# VanoDolbano.net
KiCad netlist of a schematic drawn in Altium Designer
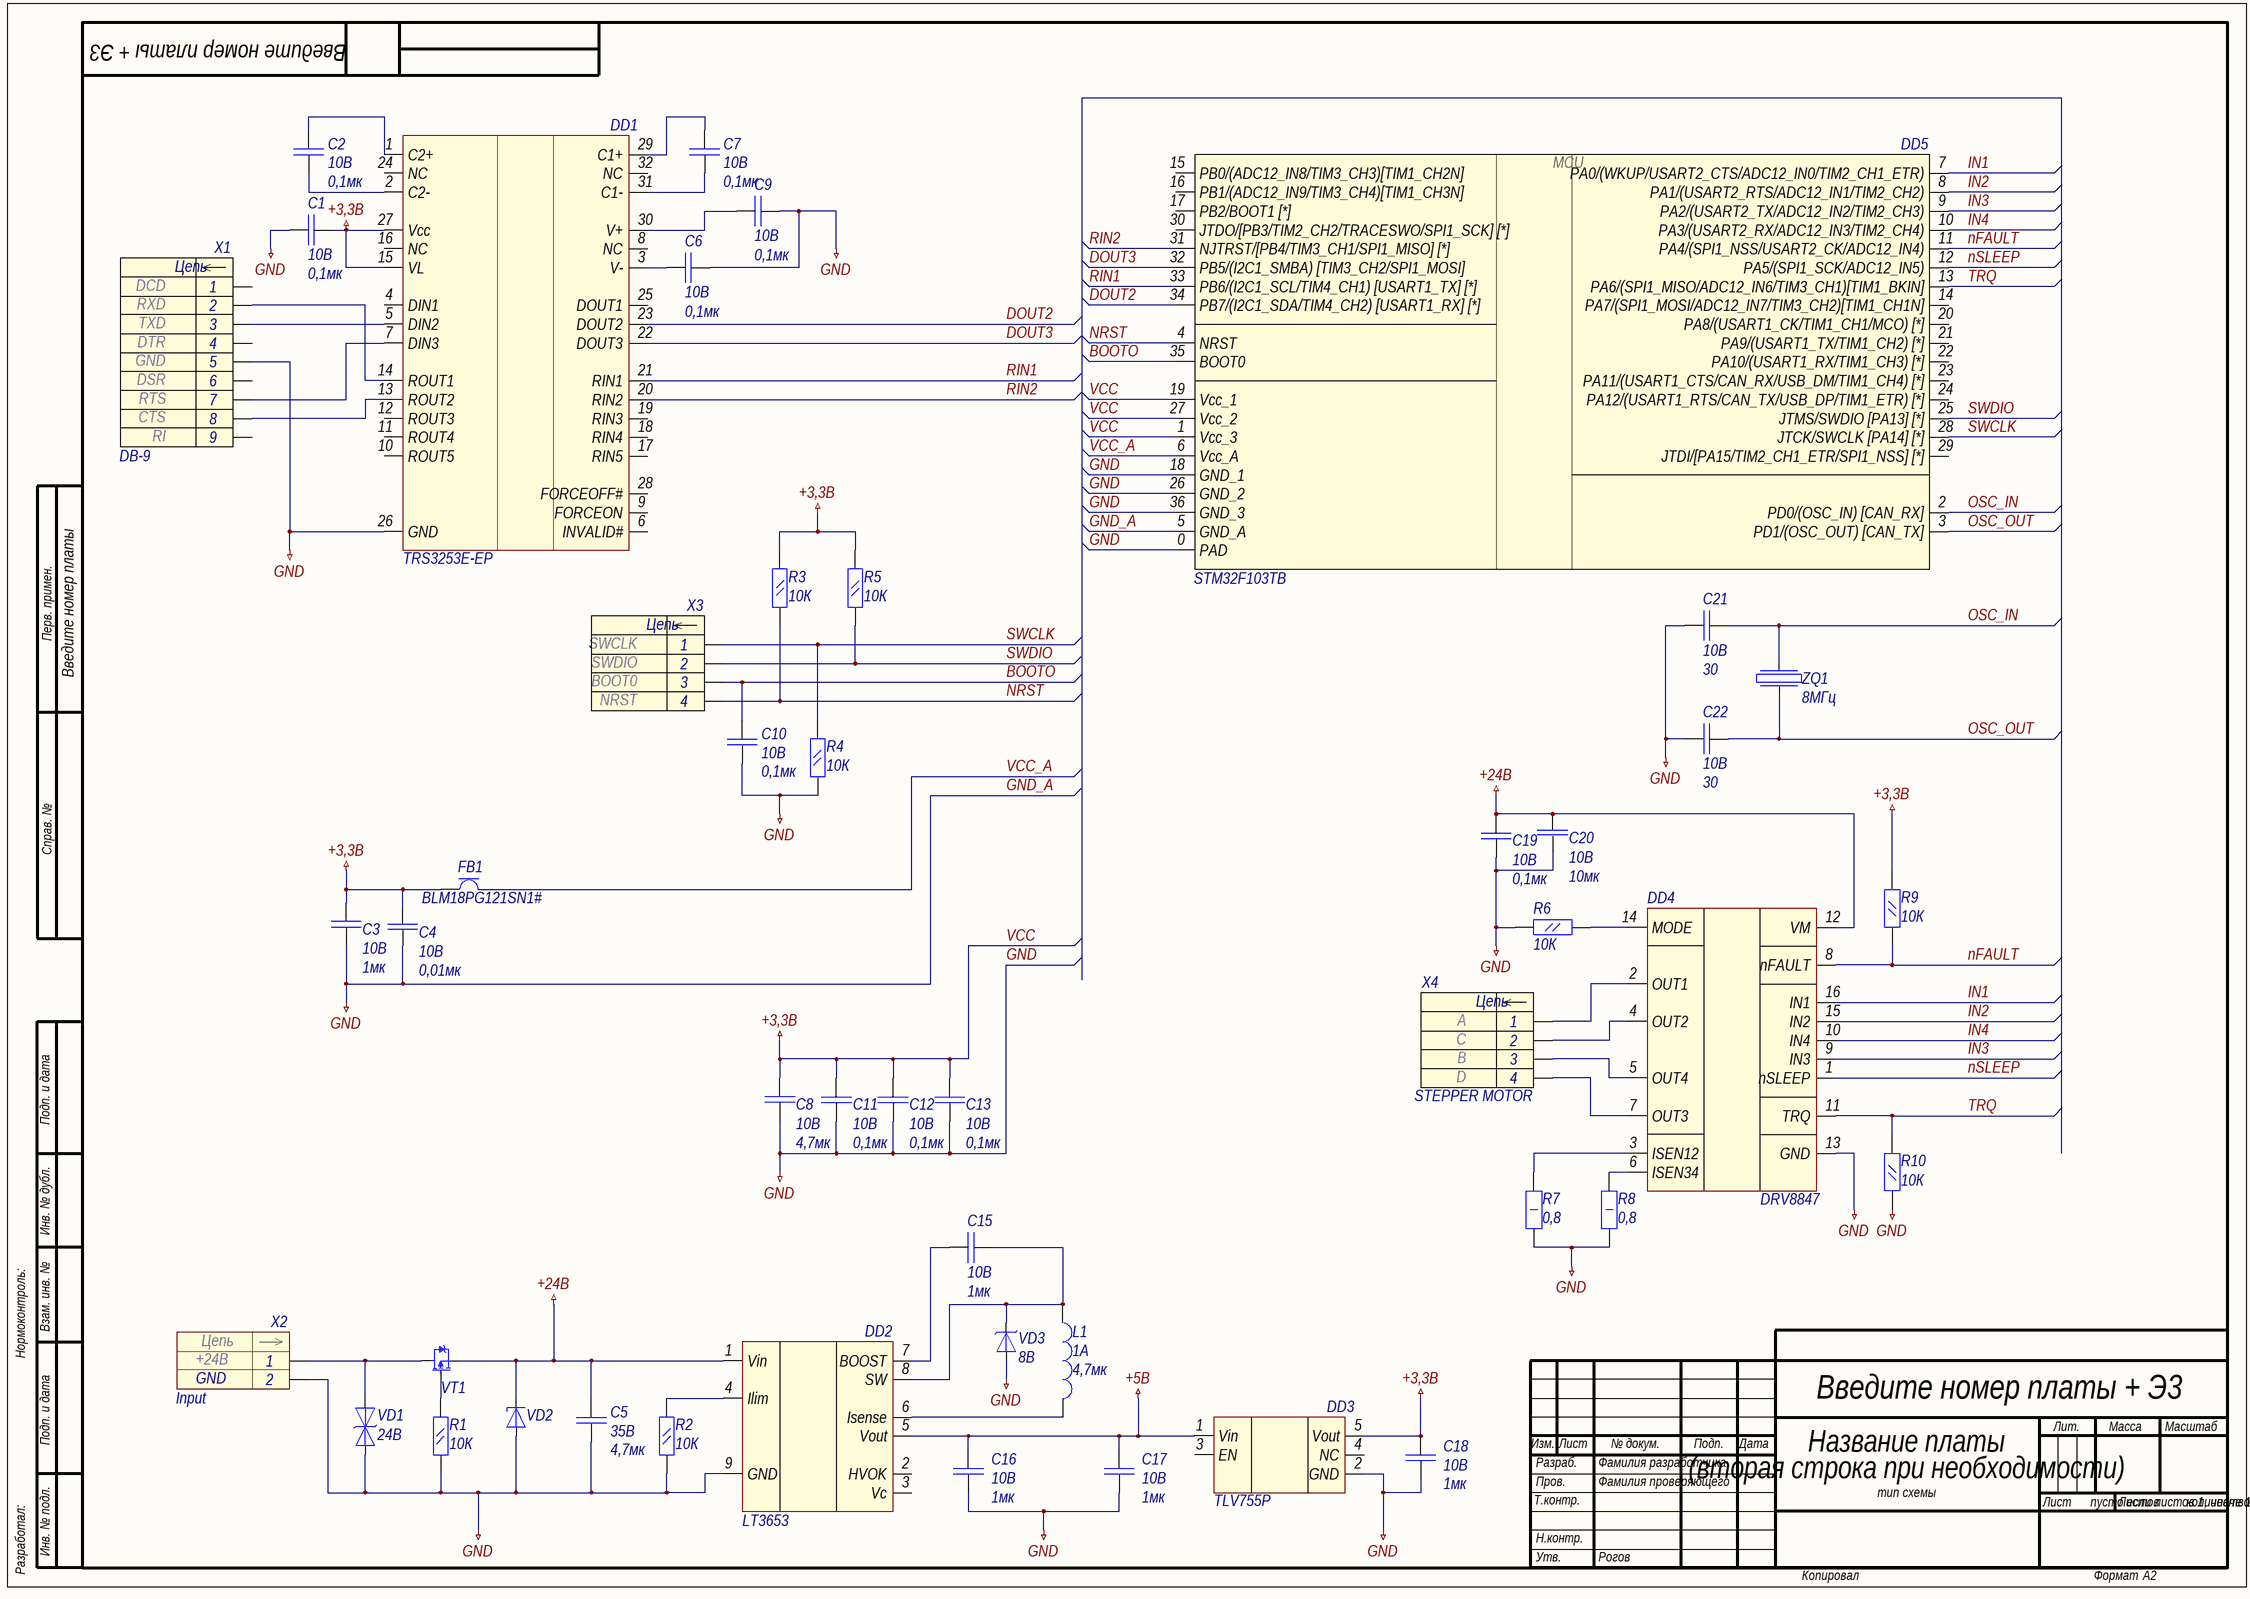
[diagram p0: VanoDolbano.schdoc]

(export (version "E")
  (design (tool "Eeschema 10.0.6"))
  (components
    (comp (ref "C1")
      (value "Capacitor")
      (footprint "CH0402C")
      (fields (field (name "VOLTAGE") "10В") (field (name "CAPACITANCE") "0,1мк"))
      (libsource (lib "GOST_Capacitors") (part "Capacitor"))
    )
    (comp (ref "C2")
      (value "Capacitor")
      (footprint "CH0402C")
      (fields (field (name "VOLTAGE") "10В") (field (name "CAPACITANCE") "0,1мк"))
      (libsource (lib "GOST_Capacitors") (part "Capacitor"))
    )
    (comp (ref "C3")
      (value "Capacitor")
      (footprint "CH0201C")
      (fields (field (name "VOLTAGE") "10В") (field (name "CAPACITANCE") "1мк"))
      (libsource (lib "GOST_Capacitors") (part "Capacitor"))
    )
    (comp (ref "C4")
      (value "Capacitor")
      (footprint "CH0402C")
      (fields (field (name "VOLTAGE") "10В") (field (name "CAPACITANCE") "0,01мк"))
      (libsource (lib "") (part "Capacitor_1"))
    )
    (comp (ref "C5")
      (value "Capacitor")
      (footprint "CH0603C")
      (fields (field (name "VOLTAGE") "35В") (field (name "CAPACITANCE") "4,7мк"))
      (libsource (lib "GOST_Capacitors") (part "Capacitor"))
    )
    (comp (ref "C6")
      (value "Capacitor")
      (footprint "CH0402C")
      (fields (field (name "VOLTAGE") "10В") (field (name "CAPACITANCE") "0,1мк"))
      (libsource (lib "GOST_Capacitors") (part "Capacitor"))
    )
    (comp (ref "C7")
      (value "Capacitor")
      (footprint "CH0402C")
      (fields (field (name "VOLTAGE") "10В") (field (name "CAPACITANCE") "0,1мк"))
      (libsource (lib "GOST_Capacitors") (part "Capacitor"))
    )
    (comp (ref "C8")
      (value "Capacitor")
      (footprint "CH0402C")
      (fields (field (name "VOLTAGE") "10В") (field (name "CAPACITANCE") "4,7мк"))
      (libsource (lib "GOST_Capacitors") (part "Capacitor"))
    )
    (comp (ref "C9")
      (value "Capacitor")
      (footprint "CH0402C")
      (fields (field (name "VOLTAGE") "10В") (field (name "CAPACITANCE") "0,1мк"))
      (libsource (lib "GOST_Capacitors") (part "Capacitor"))
    )
    (comp (ref "C10")
      (value "Capacitor")
      (footprint "CH0402C")
      (fields (field (name "VOLTAGE") "10В") (field (name "CAPACITANCE") "0,1мк"))
      (libsource (lib "GOST_Capacitors") (part "Capacitor"))
    )
    (comp (ref "C11")
      (value "Capacitor")
      (footprint "CH0402C")
      (fields (field (name "VOLTAGE") "10В") (field (name "CAPACITANCE") "0,1мк"))
      (libsource (lib "GOST_Capacitors") (part "Capacitor"))
    )
    (comp (ref "C12")
      (value "Capacitor")
      (footprint "CH0402C")
      (fields (field (name "VOLTAGE") "10В") (field (name "CAPACITANCE") "0,1мк"))
      (libsource (lib "GOST_Capacitors") (part "Capacitor"))
    )
    (comp (ref "C13")
      (value "Capacitor")
      (footprint "CH0402C")
      (fields (field (name "VOLTAGE") "10В") (field (name "CAPACITANCE") "0,1мк"))
      (libsource (lib "GOST_Capacitors") (part "Capacitor"))
    )
    (comp (ref "C15")
      (value "Capacitor")
      (footprint "CH0201C")
      (fields (field (name "VOLTAGE") "10В") (field (name "CAPACITANCE") "1мк"))
      (libsource (lib "GOST_Capacitors") (part "Capacitor"))
    )
    (comp (ref "C16")
      (value "Capacitor")
      (footprint "CH0201C")
      (fields (field (name "VOLTAGE") "10В") (field (name "CAPACITANCE") "1мк"))
      (libsource (lib "GOST_Capacitors") (part "Capacitor"))
    )
    (comp (ref "C17")
      (value "Capacitor")
      (footprint "CH0201C")
      (fields (field (name "VOLTAGE") "10В") (field (name "CAPACITANCE") "1мк"))
      (libsource (lib "GOST_Capacitors") (part "Capacitor"))
    )
    (comp (ref "C18")
      (value "Capacitor")
      (footprint "CH0201C")
      (fields (field (name "VOLTAGE") "10В") (field (name "CAPACITANCE") "1мк"))
      (libsource (lib "GOST_Capacitors") (part "Capacitor"))
    )
    (comp (ref "C19")
      (value "Capacitor")
      (footprint "CH0402C")
      (fields (field (name "VOLTAGE") "10В") (field (name "CAPACITANCE") "0,1мк"))
      (libsource (lib "GOST_Capacitors") (part "Capacitor"))
    )
    (comp (ref "C20")
      (value "Capacitor")
      (footprint "CH0402C")
      (fields (field (name "VOLTAGE") "10В") (field (name "CAPACITANCE") "10мк"))
      (libsource (lib "") (part "Capacitor_1"))
    )
    (comp (ref "C21")
      (value "Capacitor")
      (footprint "CH0201C")
      (fields (field (name "VOLTAGE") "10В") (field (name "CAPACITANCE") "30"))
      (libsource (lib "GOST_Capacitors") (part "Capacitor"))
    )
    (comp (ref "C22")
      (value "Capacitor")
      (footprint "CH0201C")
      (fields (field (name "VOLTAGE") "10В") (field (name "CAPACITANCE") "30"))
      (libsource (lib "GOST_Capacitors") (part "Capacitor"))
    )
    (comp (ref "DD1")
      (value "TRS3253E-EP")
      (footprint "TRS3253E-EP")
      (description "UART - RS232")
      (libsource (lib "GOST_lib_devices") (part "TRS3253E-EP"))
    )
    (comp (ref "DD2")
      (value "LT3653")
      (footprint "LT3653")
      (description "7.5~30 to 5")
      (libsource (lib "GOST_lib_devices") (part "LT3653"))
    )
    (comp (ref "DD3")
      (value "TLV755P")
      (footprint "SOT23-5")
      (libsource (lib "GOST_lib_devices") (part "LDO +3.3V"))
    )
    (comp (ref "DD4")
      (value "DRV8847")
      (footprint "DRV8847")
      (libsource (lib "GOST_lib_devices") (part "DRV8847"))
    )
    (comp (ref "DD5")
      (value "STM32F103TB")
      (footprint "PcbLib1:STM32_f103_36Pins")
      (description "Микроконтроллер")
      (libsource (lib "uMC") (part "STM32F103TB"))
    )
    (comp (ref "FB1")
      (value "Ferrite bead")
      (footprint "CH0603L")
      (fields (field (name "MODEL") "BLM18PG121SN1#"))
      (libsource (lib "GOST_Inductors") (part "Ferrite bead"))
    )
    (comp (ref "L1")
      (value "Inductor")
      (footprint "CH0805L")
      (fields (field (name "MAX CURRENT") "1А") (field (name "INDUCTANCE") "4,7мк"))
      (libsource (lib "GOST_Inductors") (part "Inductor"))
    )
    (comp (ref "R1")
      (value "Res_0.125")
      (footprint "CH0402R")
      (fields (field (name "IMPEDANCE") "10К"))
      (libsource (lib "GOST_Resistors") (part "Res_0.125"))
    )
    (comp (ref "R2")
      (value "Res_0.125")
      (footprint "CH0402R")
      (fields (field (name "IMPEDANCE") "10К"))
      (libsource (lib "GOST_Resistors") (part "Res_0.125"))
    )
    (comp (ref "R3")
      (value "Res_0.125")
      (footprint "CH0805R")
      (fields (field (name "IMPEDANCE") "10К"))
      (libsource (lib "") (part "Res_0.125_1"))
    )
    (comp (ref "R4")
      (value "Res_0.125")
      (footprint "CH0805R")
      (fields (field (name "IMPEDANCE") "10К"))
      (libsource (lib "") (part "Res_0.125_1"))
    )
    (comp (ref "R5")
      (value "Res_0.125")
      (footprint "CH0805R")
      (fields (field (name "IMPEDANCE") "10К"))
      (libsource (lib "") (part "Res_0.125_1"))
    )
    (comp (ref "R6")
      (value "Res_0.125")
      (footprint "CH0402R")
      (fields (field (name "IMPEDANCE") "10К"))
      (libsource (lib "GOST_Resistors") (part "Res_0.125"))
    )
    (comp (ref "R7")
      (value "Res_1")
      (footprint "CH2010R")
      (fields (field (name "POWER") "1Вт") (field (name "IMPEDANCE") "0,8"))
      (libsource (lib "GOST_Resistors") (part "Res_1"))
    )
    (comp (ref "R8")
      (value "Res_1")
      (footprint "CH2010R")
      (fields (field (name "POWER") "1Вт") (field (name "IMPEDANCE") "0,8"))
      (libsource (lib "GOST_Resistors") (part "Res_1"))
    )
    (comp (ref "R9")
      (value "Res_0.125")
      (footprint "CH0402R")
      (fields (field (name "IMPEDANCE") "10К"))
      (libsource (lib "GOST_Resistors") (part "Res_0.125"))
    )
    (comp (ref "R10")
      (value "Res_0.125")
      (footprint "CH0402R")
      (fields (field (name "IMPEDANCE") "10К"))
      (libsource (lib "GOST_Resistors") (part "Res_0.125"))
    )
    (comp (ref "VD1")
      (value "TVS-diod_simmetrical")
      (footprint "standard:SOD323")
      (fields (field (name "MANUFACTURER") "Torex Semiconductor") (field (name "THRESH_VOLTAGE") "24В"))
      (libsource (lib "GOST_Diodes") (part "TVS-diod_simmetrical"))
    )
    (comp (ref "VD2")
      (value "Diod Zener")
      (footprint "standard:SOD123")
      (libsource (lib "GOST_Diodes") (part "Diod Zener"))
    )
    (comp (ref "VD3")
      (value "TVS-diod_directed")
      (footprint "SOD123W")
      (fields (field (name "MANUFACTURER") "Nexperia") (field (name "CLAMPING_VOLTAGE") "8В"))
      (libsource (lib "GOST_Diodes") (part "TVS-diod_directed"))
    )
    (comp (ref "VT1")
      (value "P-Channel")
      (footprint "SOT23_132")
      (libsource (lib "GOST_Transistors") (part "P-Channel"))
    )
    (comp (ref "X1")
      (value "DB-9")
      (footprint "CON: DB-9F")
      (fields
        (field (name "1") "DCD")
        (field (name "2") "RXD")
        (field (name "3") "TXD")
        (field (name "4") "DTR")
        (field (name "5") "GND")
        (field (name "6") "DSR")
        (field (name "7") "RTS")
        (field (name "8") "CTS")
        (field (name "9") "RI")
      )
      (libsource (lib "GOST_lib_connectors") (part "9_pins"))
    )
    (comp (ref "X2")
      (value "Input")
      (footprint "CON: 163-179PH-EX")
      (fields (field (name "VCC") "+24В"))
      (libsource (lib "GOST_lib_connectors") (part "2_pins"))
    )
    (comp (ref "X3")
      (value "4_pins")
      (footprint "CON: CWF-4R")
      (fields
        (field (name "2") "SWDIO")
        (field (name "3") "BOOT0")
        (field (name "1") "SWCLK")
        (field (name "4") "NRST")
      )
      (libsource (lib "GOST_lib_connectors") (part "4_pins"))
    )
    (comp (ref "X4")
      (value "STEPPER MOTOR")
      (footprint "CON: CWF-4R")
      (description "Bipolar Stepper Motor 200 Step 0.35A 12VDC")
      (fields (field (name "2") "C") (field (name "3") "B") (field (name "1") "A") (field (name "4") "D"))
      (libsource (lib "GOST_lib_connectors") (part "4_pins"))
    )
    (comp (ref "ZQ1")
      (value "Oscillator")
      (footprint "OSC: 5032")
      (fields (field (name "FREQ") "8МГц"))
      (libsource (lib "GOST_Miscelanuious") (part "Oscillator"))
    )
  )
  (nets
    (net (code "1") (name "+3,3В") (class "Default")
      (node (ref "C1") (pin "2") (pinfunction "C1-_2") (pintype "power_in"))
      (node (ref "C11") (pin "1") (pinfunction "C1+_1") (pintype "power_in"))
      (node (ref "C12") (pin "1") (pinfunction "C1+_1") (pintype "power_in"))
      (node (ref "C13") (pin "1") (pinfunction "C1+_1") (pintype "power_in"))
      (node (ref "C18") (pin "1") (pinfunction "C1+_1") (pintype "power_in"))
      (node (ref "C3") (pin "2") (pinfunction "C1-_2") (pintype "power_in"))
      (node (ref "C4") (pin "1") (pinfunction "С+_1") (pintype "power_in"))
      (node (ref "C8") (pin "2") (pinfunction "C1-_2") (pintype "power_in"))
      (node (ref "DD1") (pin "15") (pinfunction "VL_15") (pintype "power_in"))
      (node (ref "DD1") (pin "27") (pinfunction "Vcc_27") (pintype "power_in"))
      (node (ref "DD3") (pin "5") (pinfunction "Vout_5") (pintype "power_in"))
      (node (ref "DD5") (pin "1") (pinfunction "Vcc_3_1") (pintype "passive"))
      (node (ref "DD5") (pin "19") (pinfunction "Vcc_1_19") (pintype "passive"))
      (node (ref "DD5") (pin "27") (pinfunction "Vcc_2_27") (pintype "passive"))
      (node (ref "FB1") (pin "1") (pintype "power_in"))
      (node (ref "R3") (pin "1") (pinfunction "C1-_1") (pintype "power_in"))
      (node (ref "R5") (pin "2") (pinfunction "C1-_2") (pintype "power_in"))
      (node (ref "R9") (pin "1") (pinfunction "1_1") (pintype "power_in"))
    )
    (net (code "2") (name "+5В") (class "Default")
      (node (ref "C16") (pin "1") (pinfunction "C1+_1") (pintype "power_in"))
      (node (ref "C17") (pin "1") (pinfunction "C1+_1") (pintype "power_in"))
      (node (ref "DD2") (pin "5") (pinfunction "Vout_5") (pintype "power_in"))
      (node (ref "DD3") (pin "1") (pinfunction "Vin_1") (pintype "power_in"))
    )
    (net (code "3") (name "+24В") (class "Default")
      (node (ref "C19") (pin "1") (pinfunction "C1+_1") (pintype "power_in"))
      (node (ref "C20") (pin "1") (pinfunction "С+_1") (pintype "power_in"))
      (node (ref "C5") (pin "1") (pinfunction "C1+_1") (pintype "power_in"))
      (node (ref "DD2") (pin "1") (pinfunction "Vin_1") (pintype "power_in"))
      (node (ref "DD4") (pin "12") (pinfunction "VM_12") (pintype "power_in"))
      (node (ref "VD2") (pin "2") (pinfunction "C_2") (pintype "passive"))
      (node (ref "VT1") (pin "3") (pinfunction "S_3") (pintype "passive"))
    )
    (net (code "4") (name "/BOOTO") (class "Default")
      (node (ref "C10") (pin "1") (pinfunction "C1+_1") (pintype "power_in"))
      (node (ref "DD5") (pin "35") (pinfunction "BOOT0_35") (pintype "passive"))
      (node (ref "X3") (pin "3") (pinfunction "3_3") (pintype "passive"))
    )
    (net (code "5") (name "/DOUT2") (class "Default")
      (node (ref "DD1") (pin "23") (pinfunction "DOUT2_23") (pintype "power_in"))
      (node (ref "DD5") (pin "34") (pinfunction "PB7/(I2C1_SDA/TIM4_CH2)_[USART1_RX]_[*]_34") (pintype "passive"))
    )
    (net (code "6") (name "/DOUT3") (class "Default")
      (node (ref "DD1") (pin "22") (pinfunction "DOUT3_22") (pintype "power_in"))
      (node (ref "DD5") (pin "32") (pinfunction "PB5/(I2C1_SMBA)_[TIM3_CH2/SPI1_MOSI]_32") (pintype "passive"))
    )
    (net (code "7") (name "/IN1") (class "Default")
      (node (ref "DD4") (pin "16") (pinfunction "IN1_16") (pintype "power_in"))
      (node (ref "DD5") (pin "7") (pinfunction "PA0/(WKUP/USART2_CTS/ADC12_IN0/TIM2_CH1_ETR)_7") (pintype "passive"))
    )
    (net (code "8") (name "/IN2") (class "Default")
      (node (ref "DD4") (pin "15") (pinfunction "IN2_15") (pintype "power_in"))
      (node (ref "DD5") (pin "8") (pinfunction "PA1/(USART2_RTS/ADC12_IN1/TIM2_CH2)_8") (pintype "passive"))
    )
    (net (code "9") (name "/IN3") (class "Default")
      (node (ref "DD4") (pin "9") (pinfunction "IN3_9") (pintype "power_in"))
      (node (ref "DD5") (pin "9") (pinfunction "PA2/(USART2_TX/ADC12_IN2/TIM2_CH3)_9") (pintype "passive"))
    )
    (net (code "10") (name "/IN4") (class "Default")
      (node (ref "DD4") (pin "10") (pinfunction "IN4_10") (pintype "power_in"))
      (node (ref "DD5") (pin "10") (pinfunction "PA3/(USART2_RX/ADC12_IN3/TIM2_CH4)_10") (pintype "passive"))
    )
    (net (code "11") (name "/NRST") (class "Default")
      (node (ref "DD5") (pin "4") (pinfunction "NRST_4") (pintype "passive"))
      (node (ref "R3") (pin "2") (pinfunction "C1-_2") (pintype "power_in"))
      (node (ref "X3") (pin "4") (pinfunction "4_4") (pintype "passive"))
    )
    (net (code "12") (name "/OSC_IN") (class "Default")
      (node (ref "C21") (pin "1") (pinfunction "C1+_1") (pintype "power_in"))
      (node (ref "DD5") (pin "2") (pinfunction "PD0/(OSC_IN)_[CAN_RX]_2") (pintype "passive"))
      (node (ref "ZQ1") (pin "1") (pintype "passive"))
    )
    (net (code "13") (name "/OSC_OUT") (class "Default")
      (node (ref "C22") (pin "1") (pinfunction "C1+_1") (pintype "power_in"))
      (node (ref "DD5") (pin "3") (pinfunction "PD1/(OSC_OUT)_[CAN_TX]_3") (pintype "passive"))
      (node (ref "ZQ1") (pin "3") (pintype "passive"))
    )
    (net (code "14") (name "/RIN1") (class "Default")
      (node (ref "DD1") (pin "21") (pinfunction "RIN1_21") (pintype "power_in"))
      (node (ref "DD5") (pin "33") (pinfunction "PB6/(I2C1_SCL/TIM4_CH1)_[USART1_TX]_[*]_33") (pintype "passive"))
    )
    (net (code "15") (name "/RIN2") (class "Default")
      (node (ref "DD1") (pin "20") (pinfunction "RIN2_20") (pintype "power_in"))
      (node (ref "DD5") (pin "31") (pinfunction "NJTRST/[PB4/TIM3_CH1/SPI1_MISO]_[*]_31") (pintype "passive"))
    )
    (net (code "16") (name "/SWCLK") (class "Default")
      (node (ref "DD5") (pin "28") (pinfunction "JTCK/SWCLK_[PA14]_[*]_28") (pintype "passive"))
      (node (ref "R4") (pin "2") (pinfunction "C1-_2") (pintype "power_in"))
      (node (ref "X3") (pin "1") (pinfunction "1_1") (pintype "passive"))
    )
    (net (code "17") (name "/SWDIO") (class "Default")
      (node (ref "DD5") (pin "25") (pinfunction "JTMS/SWDIO_[PA13]_[*]_25") (pintype "passive"))
      (node (ref "R5") (pin "1") (pinfunction "C1-_1") (pintype "power_in"))
      (node (ref "X3") (pin "2") (pinfunction "2_2") (pintype "passive"))
    )
    (net (code "18") (name "/TRQ") (class "Default")
      (node (ref "DD4") (pin "11") (pinfunction "TRQ_11") (pintype "power_in"))
      (node (ref "DD5") (pin "13") (pinfunction "PA6/(SPI1_MISO/ADC12_IN6/TIM3_CH1)[TIM1_BKIN]_13") (pintype "passive"))
      (node (ref "R10") (pin "1") (pinfunction "1_1") (pintype "power_in"))
    )
    (net (code "19") (name "/VCC_A") (class "Default")
      (node (ref "DD5") (pin "6") (pinfunction "Vcc_A_6") (pintype "passive"))
      (node (ref "FB1") (pin "2") (pintype "power_in"))
    )
    (net (code "20") (name "/nFAULT") (class "Default")
      (node (ref "DD4") (pin "8") (pinfunction "nFAULT_8") (pintype "power_in"))
      (node (ref "DD5") (pin "11") (pinfunction "PA4/(SPI1_NSS/USART2_CK/ADC12_IN4)_11") (pintype "passive"))
      (node (ref "R9") (pin "2") (pinfunction "2_2") (pintype "power_in"))
    )
    (net (code "21") (name "/nSLEEP") (class "Default")
      (node (ref "DD4") (pin "1") (pinfunction "nSLEEP_1") (pintype "power_in"))
      (node (ref "DD5") (pin "12") (pinfunction "PA5/(SPI1_SCK/ADC12_IN5)_12") (pintype "passive"))
    )
    (net (code "22") (name "GND") (class "Default")
      (node (ref "C1") (pin "1") (pinfunction "C1+_1") (pintype "power_in"))
      (node (ref "C10") (pin "2") (pinfunction "C1-_2") (pintype "power_in"))
      (node (ref "C11") (pin "2") (pinfunction "C1-_2") (pintype "power_in"))
      (node (ref "C12") (pin "2") (pinfunction "C1-_2") (pintype "power_in"))
      (node (ref "C13") (pin "2") (pinfunction "C1-_2") (pintype "power_in"))
      (node (ref "C16") (pin "2") (pinfunction "C1-_2") (pintype "power_in"))
      (node (ref "C17") (pin "2") (pinfunction "C1-_2") (pintype "power_in"))
      (node (ref "C18") (pin "2") (pinfunction "C1-_2") (pintype "power_in"))
      (node (ref "C19") (pin "2") (pinfunction "C1-_2") (pintype "power_in"))
      (node (ref "C20") (pin "2") (pinfunction "С-_2") (pintype "power_in"))
      (node (ref "C21") (pin "2") (pinfunction "C1-_2") (pintype "power_in"))
      (node (ref "C22") (pin "2") (pinfunction "C1-_2") (pintype "power_in"))
      (node (ref "C3") (pin "1") (pinfunction "C1+_1") (pintype "power_in"))
      (node (ref "C4") (pin "2") (pinfunction "С-_2") (pintype "power_in"))
      (node (ref "C5") (pin "2") (pinfunction "C1-_2") (pintype "power_in"))
      (node (ref "C6") (pin "2") (pinfunction "C1-_2") (pintype "power_in"))
      (node (ref "C8") (pin "1") (pinfunction "C1+_1") (pintype "power_in"))
      (node (ref "C9") (pin "2") (pinfunction "C1-_2") (pintype "power_in"))
      (node (ref "DD1") (pin "26") (pinfunction "GND_26") (pintype "power_in"))
      (node (ref "DD2") (pin "9") (pinfunction "GND_9") (pintype "power_in"))
      (node (ref "DD3") (pin "2") (pinfunction "GND_2") (pintype "power_in"))
      (node (ref "DD4") (pin "13") (pinfunction "GND_13") (pintype "power_in"))
      (node (ref "DD5") (pin "0") (pinfunction "PAD_0") (pintype "passive"))
      (node (ref "DD5") (pin "18") (pinfunction "GND_1_18") (pintype "passive"))
      (node (ref "DD5") (pin "26") (pinfunction "GND_2_26") (pintype "passive"))
      (node (ref "DD5") (pin "36") (pinfunction "GND_3_36") (pintype "passive"))
      (node (ref "DD5") (pin "5") (pinfunction "GND_A_5") (pintype "passive"))
      (node (ref "R1") (pin "1") (pinfunction "1_1") (pintype "power_in"))
      (node (ref "R10") (pin "2") (pinfunction "2_2") (pintype "power_in"))
      (node (ref "R2") (pin "1") (pinfunction "1_1") (pintype "power_in"))
      (node (ref "R4") (pin "1") (pinfunction "C1-_1") (pintype "power_in"))
      (node (ref "R6") (pin "1") (pinfunction "1_1") (pintype "power_in"))
      (node (ref "R7") (pin "1") (pinfunction "*_1") (pintype "power_in"))
      (node (ref "R8") (pin "1") (pinfunction "*_1") (pintype "power_in"))
      (node (ref "VD1") (pin "1") (pinfunction "A_1") (pintype "passive"))
      (node (ref "VD2") (pin "1") (pinfunction "A_1") (pintype "passive"))
      (node (ref "VD3") (pin "1") (pinfunction "A_1") (pintype "passive"))
      (node (ref "X1") (pin "5") (pinfunction "5_5") (pintype "passive"))
      (node (ref "X2") (pin "2") (pinfunction "2_2") (pintype "passive"))
    )
    (net (code "23") (name "Net-(C2-C1+)") (class "Default")
      (node (ref "C2") (pin "1") (pinfunction "C1+_1") (pintype "power_in"))
      (node (ref "DD1") (pin "1") (pinfunction "C2+_1") (pintype "power_in"))
    )
    (net (code "24") (name "Net-(C2-C1-)") (class "Default")
      (node (ref "C2") (pin "2") (pinfunction "C1-_2") (pintype "power_in"))
      (node (ref "DD1") (pin "2") (pinfunction "C2-_2") (pintype "power_in"))
    )
    (net (code "25") (name "Net-(C6-C1+)") (class "Default")
      (node (ref "C6") (pin "1") (pinfunction "C1+_1") (pintype "power_in"))
      (node (ref "DD1") (pin "3") (pinfunction "V-_3") (pintype "power_in"))
    )
    (net (code "26") (name "Net-(C7-C1+)") (class "Default")
      (node (ref "C7") (pin "1") (pinfunction "C1+_1") (pintype "power_in"))
      (node (ref "DD1") (pin "29") (pinfunction "C1+_29") (pintype "power_in"))
    )
    (net (code "27") (name "Net-(C7-C1-)") (class "Default")
      (node (ref "C7") (pin "2") (pinfunction "C1-_2") (pintype "power_in"))
      (node (ref "DD1") (pin "31") (pinfunction "C1-_31") (pintype "power_in"))
    )
    (net (code "28") (name "Net-(C9-C1+)") (class "Default")
      (node (ref "C9") (pin "1") (pinfunction "C1+_1") (pintype "power_in"))
      (node (ref "DD1") (pin "30") (pinfunction "V+_30") (pintype "power_in"))
    )
    (net (code "29") (name "Net-(C15-C1+)") (class "Default")
      (node (ref "C15") (pin "1") (pinfunction "C1+_1") (pintype "power_in"))
      (node (ref "DD2") (pin "7") (pinfunction "BOOST_7") (pintype "power_in"))
    )
    (net (code "30") (name "Net-(C15-C1-)") (class "Default")
      (node (ref "C15") (pin "2") (pinfunction "C1-_2") (pintype "power_in"))
      (node (ref "DD2") (pin "8") (pinfunction "SW_8") (pintype "power_in"))
      (node (ref "L1") (pin "1") (pinfunction "1_1") (pintype "power_in"))
      (node (ref "VD3") (pin "2") (pinfunction "C_2") (pintype "passive"))
    )
    (net (code "31") (name "Net-(DD1-DIN2)") (class "Default")
      (node (ref "DD1") (pin "5") (pinfunction "DIN2_5") (pintype "power_in"))
      (node (ref "X1") (pin "3") (pinfunction "3_3") (pintype "passive"))
    )
    (net (code "32") (name "Net-(DD1-DIN3)") (class "Default")
      (node (ref "DD1") (pin "7") (pinfunction "DIN3_7") (pintype "power_in"))
      (node (ref "X1") (pin "7") (pinfunction "7_7") (pintype "power_in"))
    )
    (net (code "33") (name "Net-(DD1-ROUT1)") (class "Default")
      (node (ref "DD1") (pin "14") (pinfunction "ROUT1_14") (pintype "power_in"))
      (node (ref "X1") (pin "2") (pinfunction "2_2") (pintype "passive"))
    )
    (net (code "34") (name "Net-(DD1-ROUT2)") (class "Default")
      (node (ref "DD1") (pin "13") (pinfunction "ROUT2_13") (pintype "power_in"))
      (node (ref "X1") (pin "8") (pinfunction "8_8") (pintype "power_in"))
    )
    (net (code "35") (name "Net-(DD2-Ilim)") (class "Default")
      (node (ref "DD2") (pin "4") (pinfunction "Ilim_4") (pintype "power_in"))
      (node (ref "R2") (pin "2") (pinfunction "2_2") (pintype "power_in"))
    )
    (net (code "36") (name "Net-(DD2-Isense)") (class "Default")
      (node (ref "DD2") (pin "6") (pinfunction "Isense_6") (pintype "power_in"))
      (node (ref "L1") (pin "2") (pinfunction "2_2") (pintype "power_in"))
    )
    (net (code "37") (name "Net-(DD4-ISEN12)") (class "Default")
      (node (ref "DD4") (pin "3") (pinfunction "ISEN12_3") (pintype "power_in"))
      (node (ref "R7") (pin "2") (pinfunction "*_2") (pintype "power_in"))
    )
    (net (code "38") (name "Net-(DD4-ISEN34)") (class "Default")
      (node (ref "DD4") (pin "6") (pinfunction "ISEN34_6") (pintype "power_in"))
      (node (ref "R8") (pin "2") (pinfunction "*_2") (pintype "power_in"))
    )
    (net (code "39") (name "Net-(DD4-MODE)") (class "Default")
      (node (ref "DD4") (pin "14") (pinfunction "MODE_14") (pintype "power_in"))
      (node (ref "R6") (pin "2") (pinfunction "2_2") (pintype "power_in"))
    )
    (net (code "40") (name "Net-(DD4-OUT1)") (class "Default")
      (node (ref "DD4") (pin "2") (pinfunction "OUT1_2") (pintype "power_in"))
      (node (ref "X4") (pin "1") (pinfunction "1_1") (pintype "passive"))
    )
    (net (code "41") (name "Net-(DD4-OUT2)") (class "Default")
      (node (ref "DD4") (pin "4") (pinfunction "OUT2_4") (pintype "power_in"))
      (node (ref "X4") (pin "2") (pinfunction "2_2") (pintype "passive"))
    )
    (net (code "42") (name "Net-(DD4-OUT3)") (class "Default")
      (node (ref "DD4") (pin "7") (pinfunction "OUT3_7") (pintype "power_in"))
      (node (ref "X4") (pin "4") (pinfunction "4_4") (pintype "passive"))
    )
    (net (code "43") (name "Net-(DD4-OUT4)") (class "Default")
      (node (ref "DD4") (pin "5") (pinfunction "OUT4_5") (pintype "power_in"))
      (node (ref "X4") (pin "3") (pinfunction "3_3") (pintype "passive"))
    )
    (net (code "44") (name "Net-(VD1-C)") (class "Default")
      (node (ref "VD1") (pin "2") (pinfunction "C_2") (pintype "passive"))
      (node (ref "VT1") (pin "2") (pinfunction "D_2") (pintype "passive"))
      (node (ref "X2") (pin "1") (pinfunction "1_1") (pintype "passive"))
    )
    (net (code "45") (name "Net-(VT1-G)") (class "Default")
      (node (ref "R1") (pin "2") (pinfunction "2_2") (pintype "power_in"))
      (node (ref "VT1") (pin "1") (pinfunction "G_1") (pintype "passive"))
    )
    (net (code "46") (name "unconnected-(DD1-DIN1-Pad4)") (class "Default")
      (node (ref "DD1") (pin "4") (pinfunction "DIN1_4") (pintype "power_in"))
    )
    (net (code "47") (name "unconnected-(DD1-DOUT1-Pad25)") (class "Default")
      (node (ref "DD1") (pin "25") (pinfunction "DOUT1_25") (pintype "power_in"))
    )
    (net (code "48") (name "unconnected-(DD1-FORCEOFF#-Pad28)") (class "Default")
      (node (ref "DD1") (pin "28") (pinfunction "FORCEOFF#_28") (pintype "power_in"))
    )
    (net (code "49") (name "unconnected-(DD1-FORCEON-Pad9)") (class "Default")
      (node (ref "DD1") (pin "9") (pinfunction "FORCEON_9") (pintype "power_in"))
    )
    (net (code "50") (name "unconnected-(DD1-INVALID#-Pad6)") (class "Default")
      (node (ref "DD1") (pin "6") (pinfunction "INVALID#_6") (pintype "power_in"))
    )
    (net (code "51") (name "unconnected-(DD1-NC-Pad8)") (class "Default")
      (node (ref "DD1") (pin "8") (pinfunction "NC_8") (pintype "power_in"))
    )
    (net (code "52") (name "unconnected-(DD1-NC-Pad16)") (class "Default")
      (node (ref "DD1") (pin "16") (pinfunction "NC_16") (pintype "power_in"))
    )
    (net (code "53") (name "unconnected-(DD1-NC-Pad24)") (class "Default")
      (node (ref "DD1") (pin "24") (pinfunction "NC_24") (pintype "power_in"))
    )
    (net (code "54") (name "unconnected-(DD1-NC-Pad32)") (class "Default")
      (node (ref "DD1") (pin "32") (pinfunction "NC_32") (pintype "power_in"))
    )
    (net (code "55") (name "unconnected-(DD1-RIN3-Pad19)") (class "Default")
      (node (ref "DD1") (pin "19") (pinfunction "RIN3_19") (pintype "power_in"))
    )
    (net (code "56") (name "unconnected-(DD1-RIN4-Pad18)") (class "Default")
      (node (ref "DD1") (pin "18") (pinfunction "RIN4_18") (pintype "power_in"))
    )
    (net (code "57") (name "unconnected-(DD1-RIN5-Pad17)") (class "Default")
      (node (ref "DD1") (pin "17") (pinfunction "RIN5_17") (pintype "power_in"))
    )
    (net (code "58") (name "unconnected-(DD1-ROUT3-Pad12)") (class "Default")
      (node (ref "DD1") (pin "12") (pinfunction "ROUT3_12") (pintype "power_in"))
    )
    (net (code "59") (name "unconnected-(DD1-ROUT4-Pad11)") (class "Default")
      (node (ref "DD1") (pin "11") (pinfunction "ROUT4_11") (pintype "power_in"))
    )
    (net (code "60") (name "unconnected-(DD1-ROUT5-Pad10)") (class "Default")
      (node (ref "DD1") (pin "10") (pinfunction "ROUT5_10") (pintype "power_in"))
    )
    (net (code "61") (name "unconnected-(DD2-HVOK-Pad2)") (class "Default")
      (node (ref "DD2") (pin "2") (pinfunction "HVOK_2") (pintype "power_in"))
    )
    (net (code "62") (name "unconnected-(DD2-Vc-Pad3)") (class "Default")
      (node (ref "DD2") (pin "3") (pinfunction "Vc_3") (pintype "power_in"))
    )
    (net (code "63") (name "unconnected-(DD3-EN-Pad3)") (class "Default")
      (node (ref "DD3") (pin "3") (pinfunction "EN_3") (pintype "power_in"))
    )
    (net (code "64") (name "unconnected-(DD3-NC-Pad4)") (class "Default")
      (node (ref "DD3") (pin "4") (pinfunction "NC_4") (pintype "power_in"))
    )
    (net (code "65") (name "unconnected-(DD5-JTDI{slash}[PA15{slash}TIM2_CH1_ETR{slash}SPI1_NSS]_[*]-Pad29)") (class "Default")
      (node (ref "DD5") (pin "29") (pinfunction "JTDI/[PA15/TIM2_CH1_ETR/SPI1_NSS]_[*]_29") (pintype "passive"))
    )
    (net (code "66") (name "unconnected-(DD5-JTDO{slash}[PB3{slash}TIM2_CH2{slash}TRACESWO{slash}SPI1_SCK]_[*]-Pad30)") (class "Default")
      (node (ref "DD5") (pin "30") (pinfunction "JTDO/[PB3/TIM2_CH2/TRACESWO/SPI1_SCK]_[*]_30") (pintype "passive"))
    )
    (net (code "67") (name "unconnected-(DD5-PA7{slash}(SPI1_MOSI{slash}ADC12_IN7{slash}TIM3_CH2)[TIM1_CH1N]-Pad14)") (class "Default")
      (node (ref "DD5") (pin "14") (pinfunction "PA7/(SPI1_MOSI/ADC12_IN7/TIM3_CH2)[TIM1_CH1N]_14") (pintype "passive"))
    )
    (net (code "68") (name "unconnected-(DD5-PA8{slash}(USART1_CK{slash}TIM1_CH1{slash}MCO)_[*]-Pad20)") (class "Default")
      (node (ref "DD5") (pin "20") (pinfunction "PA8/(USART1_CK/TIM1_CH1/MCO)_[*]_20") (pintype "passive"))
    )
    (net (code "69") (name "unconnected-(DD5-PA9{slash}(USART1_TX{slash}TIM1_CH2)_[*]-Pad21)") (class "Default")
      (node (ref "DD5") (pin "21") (pinfunction "PA9/(USART1_TX/TIM1_CH2)_[*]_21") (pintype "passive"))
    )
    (net (code "70") (name "unconnected-(DD5-PA10{slash}(USART1_RX{slash}TIM1_CH3)_[*]-Pad22)") (class "Default")
      (node (ref "DD5") (pin "22") (pinfunction "PA10/(USART1_RX/TIM1_CH3)_[*]_22") (pintype "passive"))
    )
    (net (code "71") (name "unconnected-(DD5-PA11{slash}(USART1_CTS{slash}CAN_RX{slash}USB_DM{slash}TIM1_CH4)_[*]-Pad23)") (class "Default")
      (node (ref "DD5") (pin "23") (pinfunction "PA11/(USART1_CTS/CAN_RX/USB_DM/TIM1_CH4)_[*]_23") (pintype "passive"))
    )
    (net (code "72") (name "unconnected-(DD5-PA12{slash}(USART1_RTS{slash}CAN_TX{slash}USB_DP{slash}TIM1_ETR)_[*]-Pad24)") (class "Default")
      (node (ref "DD5") (pin "24") (pinfunction "PA12/(USART1_RTS/CAN_TX/USB_DP/TIM1_ETR)_[*]_24") (pintype "passive"))
    )
    (net (code "73") (name "unconnected-(DD5-PB0{slash}(ADC12_IN8{slash}TIM3_CH3)[TIM1_CH2N]-Pad15)") (class "Default")
      (node (ref "DD5") (pin "15") (pinfunction "PB0/(ADC12_IN8/TIM3_CH3)[TIM1_CH2N]_15") (pintype "passive"))
    )
    (net (code "74") (name "unconnected-(DD5-PB1{slash}(ADC12_IN9{slash}TIM3_CH4)[TIM1_CH3N]-Pad16)") (class "Default")
      (node (ref "DD5") (pin "16") (pinfunction "PB1/(ADC12_IN9/TIM3_CH4)[TIM1_CH3N]_16") (pintype "passive"))
    )
    (net (code "75") (name "unconnected-(DD5-PB2{slash}BOOT1_[*]-Pad17)") (class "Default")
      (node (ref "DD5") (pin "17") (pinfunction "PB2/BOOT1_[*]_17") (pintype "passive"))
    )
    (net (code "76") (name "unconnected-(X1-Pad1)") (class "Default")
      (node (ref "X1") (pin "1") (pinfunction "1_1") (pintype "passive"))
    )
    (net (code "77") (name "unconnected-(X1-Pad4)") (class "Default")
      (node (ref "X1") (pin "4") (pinfunction "4_4") (pintype "passive"))
    )
    (net (code "78") (name "unconnected-(X1-Pad6)") (class "Default")
      (node (ref "X1") (pin "6") (pinfunction "6_6") (pintype "passive"))
    )
    (net (code "79") (name "unconnected-(X1-Pad9)") (class "Default")
      (node (ref "X1") (pin "9") (pinfunction "9_9") (pintype "power_in"))
    )
  )
)
